# User_Interface.net
KiCad netlist of a schematic drawn in EAGLE
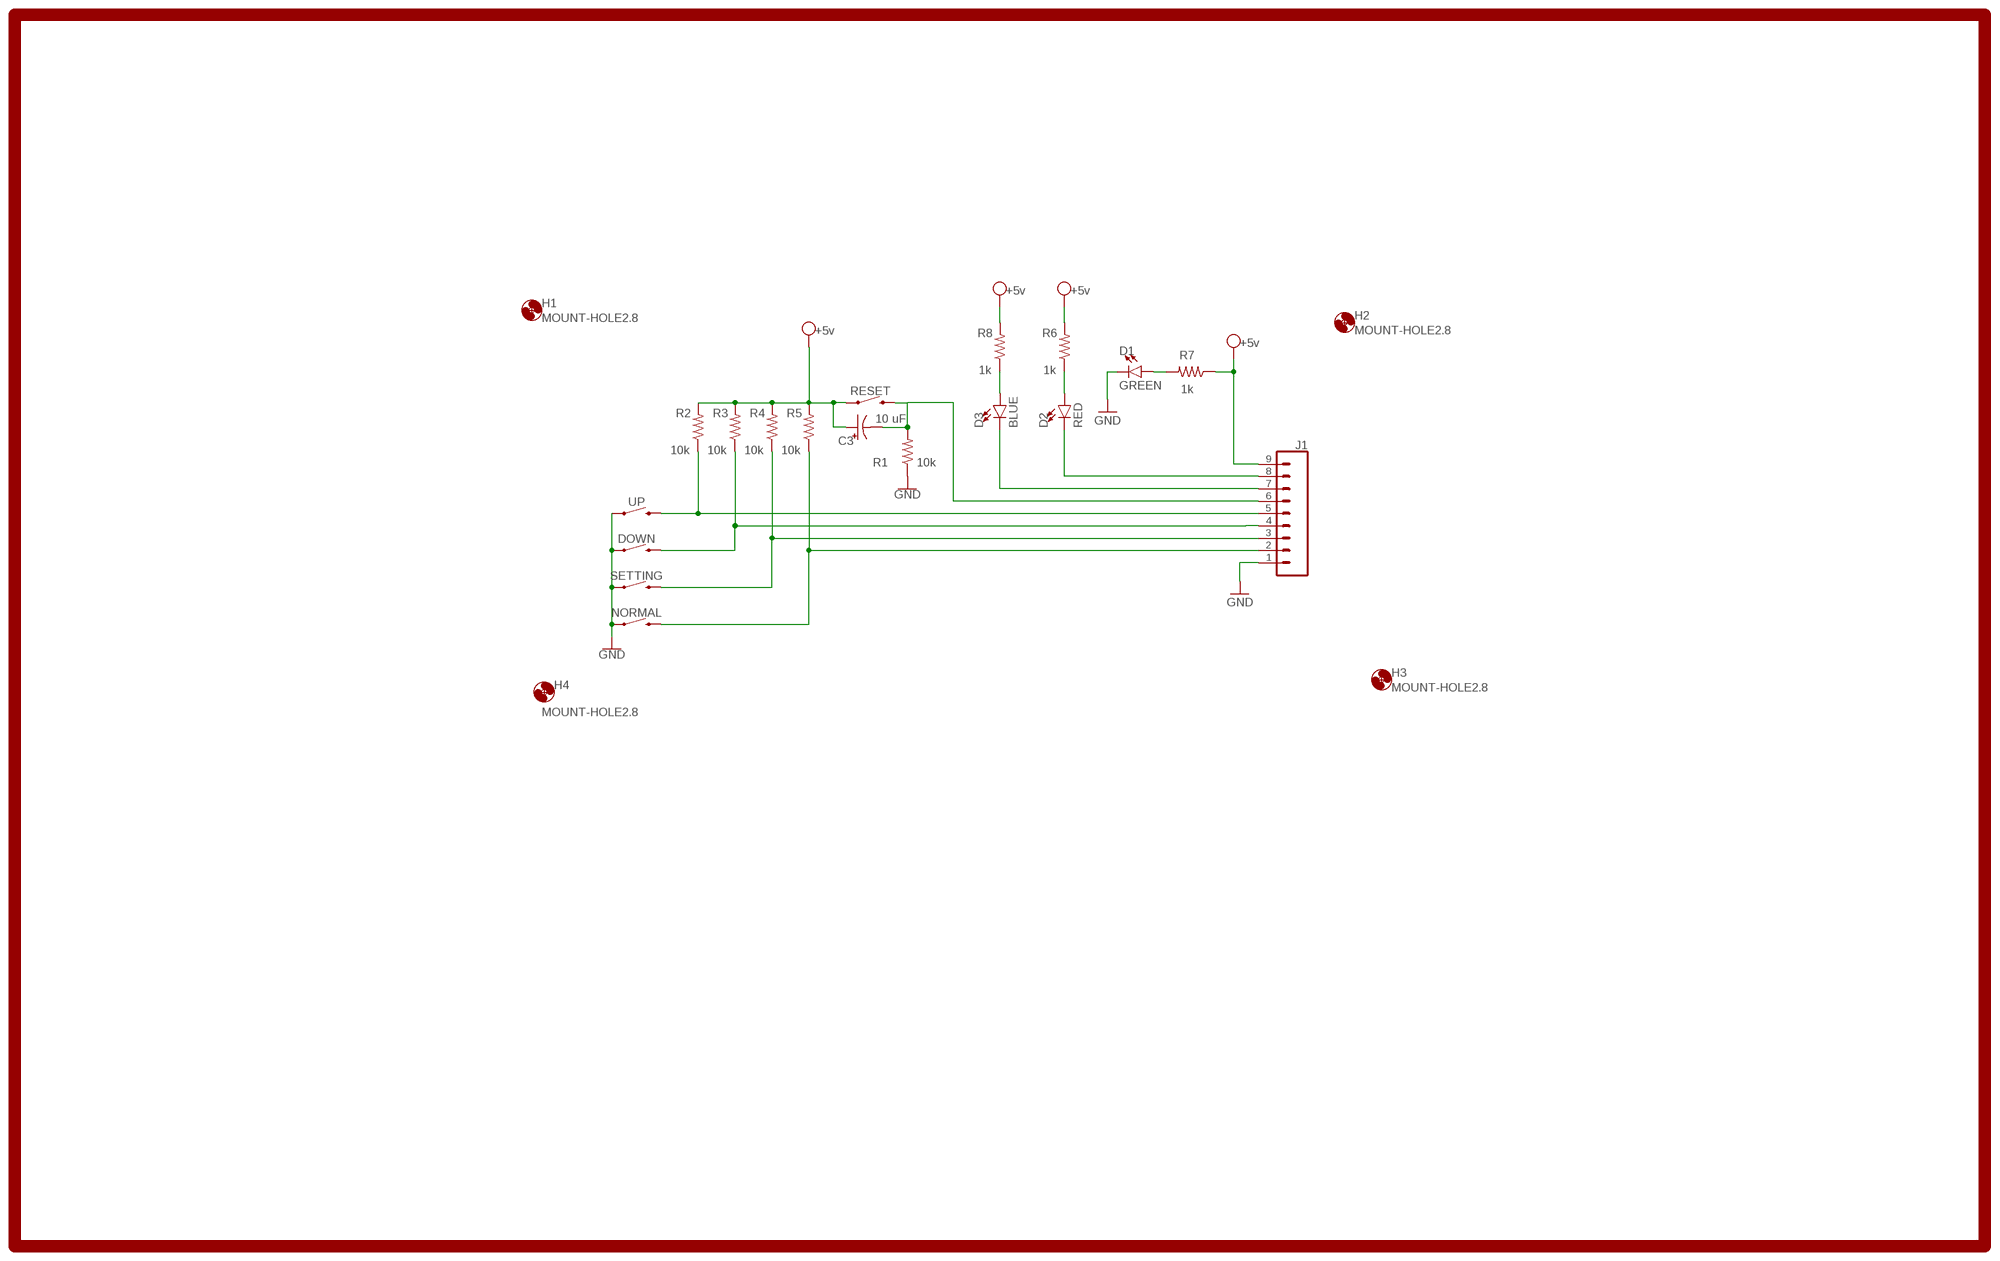
[diagram p0: schematic, sheet 1]

(export (version "E")
  (design (tool "Eeschema 10.0.6"))
  (components
    (comp (ref "C3")
      (value "10 uF")
      (footprint "eagle-import:TT2D6")
      (libsource (lib "eagle-import") (part "CPOL-USTT2D6"))
    )
    (comp (ref "D1")
      (value "GREEN")
      (footprint "eagle-import:LED-1206")
      (libsource (lib "eagle-import") (part "LED-GREENLILYPAD"))
    )
    (comp (ref "D2")
      (value "RED")
      (footprint "eagle-import:LED-1206")
      (libsource (lib "eagle-import") (part "LED-RED1206"))
    )
    (comp (ref "D3")
      (value "BLUE")
      (footprint "eagle-import:LED-1206")
      (libsource (lib "eagle-import") (part "LED-BLUE1206"))
    )
    (comp (ref "DOWN")
      (value "MOMENTARY-SWITCH-SPST-PTH-6.0MM")
      (footprint "eagle-import:TACTILE_SWITCH_PTH_6.0MM")
      (libsource (lib "eagle-import") (part "MOMENTARY-SWITCH-SPST-PTH-6.0MM"))
    )
    (comp (ref "H1")
      (value "MOUNT-HOLE2.8")
      (footprint "eagle-import:2,8")
      (libsource (lib "eagle-import") (part "MOUNT-HOLE2.8"))
    )
    (comp (ref "H2")
      (value "MOUNT-HOLE2.8")
      (footprint "eagle-import:2,8")
      (libsource (lib "eagle-import") (part "MOUNT-HOLE2.8"))
    )
    (comp (ref "H3")
      (value "MOUNT-HOLE2.8")
      (footprint "eagle-import:2,8")
      (libsource (lib "eagle-import") (part "MOUNT-HOLE2.8"))
    )
    (comp (ref "H4")
      (value "MOUNT-HOLE2.8")
      (footprint "eagle-import:2,8")
      (libsource (lib "eagle-import") (part "MOUNT-HOLE2.8"))
    )
    (comp (ref "J1")
      (value "CONN_09")
      (footprint "eagle-import:1X09")
      (libsource (lib "eagle-import") (part "CONN_09"))
    )
    (comp (ref "NORMAL")
      (value "MOMENTARY-SWITCH-SPST-PTH-6.0MM")
      (footprint "eagle-import:TACTILE_SWITCH_PTH_6.0MM")
      (libsource (lib "eagle-import") (part "MOMENTARY-SWITCH-SPST-PTH-6.0MM"))
    )
    (comp (ref "R1")
      (value "10k")
      (footprint "eagle-import:R0603")
      (libsource (lib "eagle-import") (part "R-US_R0603"))
    )
    (comp (ref "R2")
      (value "10k")
      (footprint "eagle-import:R0603")
      (libsource (lib "eagle-import") (part "R-US_R0603"))
    )
    (comp (ref "R3")
      (value "10k")
      (footprint "eagle-import:R0603")
      (libsource (lib "eagle-import") (part "R-US_R0603"))
    )
    (comp (ref "R4")
      (value "10k")
      (footprint "eagle-import:R0603")
      (libsource (lib "eagle-import") (part "R-US_R0603"))
    )
    (comp (ref "R5")
      (value "10k")
      (footprint "eagle-import:R0603")
      (libsource (lib "eagle-import") (part "R-US_R0603"))
    )
    (comp (ref "R6")
      (value "1k")
      (footprint "eagle-import:R0603")
      (libsource (lib "eagle-import") (part "R-US_R0603"))
    )
    (comp (ref "R7")
      (value "1k")
      (footprint "eagle-import:R0603")
      (libsource (lib "eagle-import") (part "R-US_R0603"))
    )
    (comp (ref "R8")
      (value "1k")
      (footprint "eagle-import:R0603")
      (libsource (lib "eagle-import") (part "R-US_R0603"))
    )
    (comp (ref "RESET")
      (value "MOMENTARY-SWITCH-SPST-PTH-6.0MM")
      (footprint "eagle-import:TACTILE_SWITCH_PTH_6.0MM")
      (libsource (lib "eagle-import") (part "MOMENTARY-SWITCH-SPST-PTH-6.0MM"))
    )
    (comp (ref "SETTING")
      (value "MOMENTARY-SWITCH-SPST-PTH-6.0MM")
      (footprint "eagle-import:TACTILE_SWITCH_PTH_6.0MM")
      (libsource (lib "eagle-import") (part "MOMENTARY-SWITCH-SPST-PTH-6.0MM"))
    )
    (comp (ref "UP")
      (value "MOMENTARY-SWITCH-SPST-PTH-6.0MM")
      (footprint "eagle-import:TACTILE_SWITCH_PTH_6.0MM")
      (libsource (lib "eagle-import") (part "MOMENTARY-SWITCH-SPST-PTH-6.0MM"))
    )
  )
  (nets
    (net (code "1") (name "+5v") (class "Default")
      (node (ref "C3") (pin "+") (pinfunction "+_+") (pintype "passive"))
      (node (ref "J1") (pin "9") (pinfunction "9_9") (pintype "passive"))
      (node (ref "R2") (pin "2") (pinfunction "2_2") (pintype "passive"))
      (node (ref "R3") (pin "2") (pinfunction "2_2") (pintype "passive"))
      (node (ref "R4") (pin "2") (pinfunction "2_2") (pintype "passive"))
      (node (ref "R5") (pin "2") (pinfunction "2_2") (pintype "passive"))
      (node (ref "R6") (pin "2") (pinfunction "2_2") (pintype "passive"))
      (node (ref "R7") (pin "1") (pinfunction "1_1") (pintype "passive"))
      (node (ref "R8") (pin "2") (pinfunction "2_2") (pintype "passive"))
      (node (ref "RESET") (pin "1") (pinfunction "1_1") (pintype "passive"))
    )
    (net (code "2") (name "GND") (class "Default")
      (node (ref "D1") (pin "C") (pinfunction "C_C") (pintype "passive"))
      (node (ref "DOWN") (pin "1") (pinfunction "1_1") (pintype "passive"))
      (node (ref "J1") (pin "1") (pinfunction "1_1") (pintype "passive"))
      (node (ref "NORMAL") (pin "1") (pinfunction "1_1") (pintype "passive"))
      (node (ref "R1") (pin "1") (pinfunction "1_1") (pintype "passive"))
      (node (ref "SETTING") (pin "1") (pinfunction "1_1") (pintype "passive"))
      (node (ref "UP") (pin "1") (pinfunction "1_1") (pintype "passive"))
    )
    (net (code "3") (name "Net-(D1-PadA)") (class "Default")
      (node (ref "D1") (pin "A") (pinfunction "A_A") (pintype "passive"))
      (node (ref "R7") (pin "2") (pinfunction "2_2") (pintype "passive"))
    )
    (net (code "4") (name "Net-(D2-PadA)") (class "Default")
      (node (ref "D2") (pin "A") (pinfunction "A_A") (pintype "passive"))
      (node (ref "R6") (pin "1") (pinfunction "1_1") (pintype "passive"))
    )
    (net (code "5") (name "Net-(D2-PadC)") (class "Default")
      (node (ref "D2") (pin "C") (pinfunction "C_C") (pintype "passive"))
      (node (ref "J1") (pin "8") (pinfunction "8_8") (pintype "passive"))
    )
    (net (code "6") (name "Net-(D3-PadA)") (class "Default")
      (node (ref "D3") (pin "A") (pinfunction "A_A") (pintype "passive"))
      (node (ref "R8") (pin "1") (pinfunction "1_1") (pintype "passive"))
    )
    (net (code "7") (name "Net-(D3-PadC)") (class "Default")
      (node (ref "D3") (pin "C") (pinfunction "C_C") (pintype "passive"))
      (node (ref "J1") (pin "7") (pinfunction "7_7") (pintype "passive"))
    )
    (net (code "8") (name "Net-(DOWN-2)") (class "Default")
      (node (ref "DOWN") (pin "3") (pinfunction "2_3") (pintype "passive"))
      (node (ref "J1") (pin "4") (pinfunction "4_4") (pintype "passive"))
      (node (ref "R3") (pin "1") (pinfunction "1_1") (pintype "passive"))
    )
    (net (code "9") (name "Net-(NORMAL-2)") (class "Default")
      (node (ref "J1") (pin "2") (pinfunction "2_2") (pintype "passive"))
      (node (ref "NORMAL") (pin "3") (pinfunction "2_3") (pintype "passive"))
      (node (ref "R5") (pin "1") (pinfunction "1_1") (pintype "passive"))
    )
    (net (code "10") (name "Net-(RESET-2)") (class "Default")
      (node (ref "C3") (pin "-") (pinfunction "-_-") (pintype "passive"))
      (node (ref "J1") (pin "6") (pinfunction "6_6") (pintype "passive"))
      (node (ref "R1") (pin "2") (pinfunction "2_2") (pintype "passive"))
      (node (ref "RESET") (pin "3") (pinfunction "2_3") (pintype "passive"))
    )
    (net (code "11") (name "Net-(SETTING-2)") (class "Default")
      (node (ref "J1") (pin "3") (pinfunction "3_3") (pintype "passive"))
      (node (ref "R4") (pin "1") (pinfunction "1_1") (pintype "passive"))
      (node (ref "SETTING") (pin "3") (pinfunction "2_3") (pintype "passive"))
    )
    (net (code "12") (name "Net-(UP-2)") (class "Default")
      (node (ref "J1") (pin "5") (pinfunction "5_5") (pintype "passive"))
      (node (ref "R2") (pin "1") (pinfunction "1_1") (pintype "passive"))
      (node (ref "UP") (pin "3") (pinfunction "2_3") (pintype "passive"))
    )
  )
)
